# source_eagle.net
KiCad netlist of a schematic drawn in EAGLE
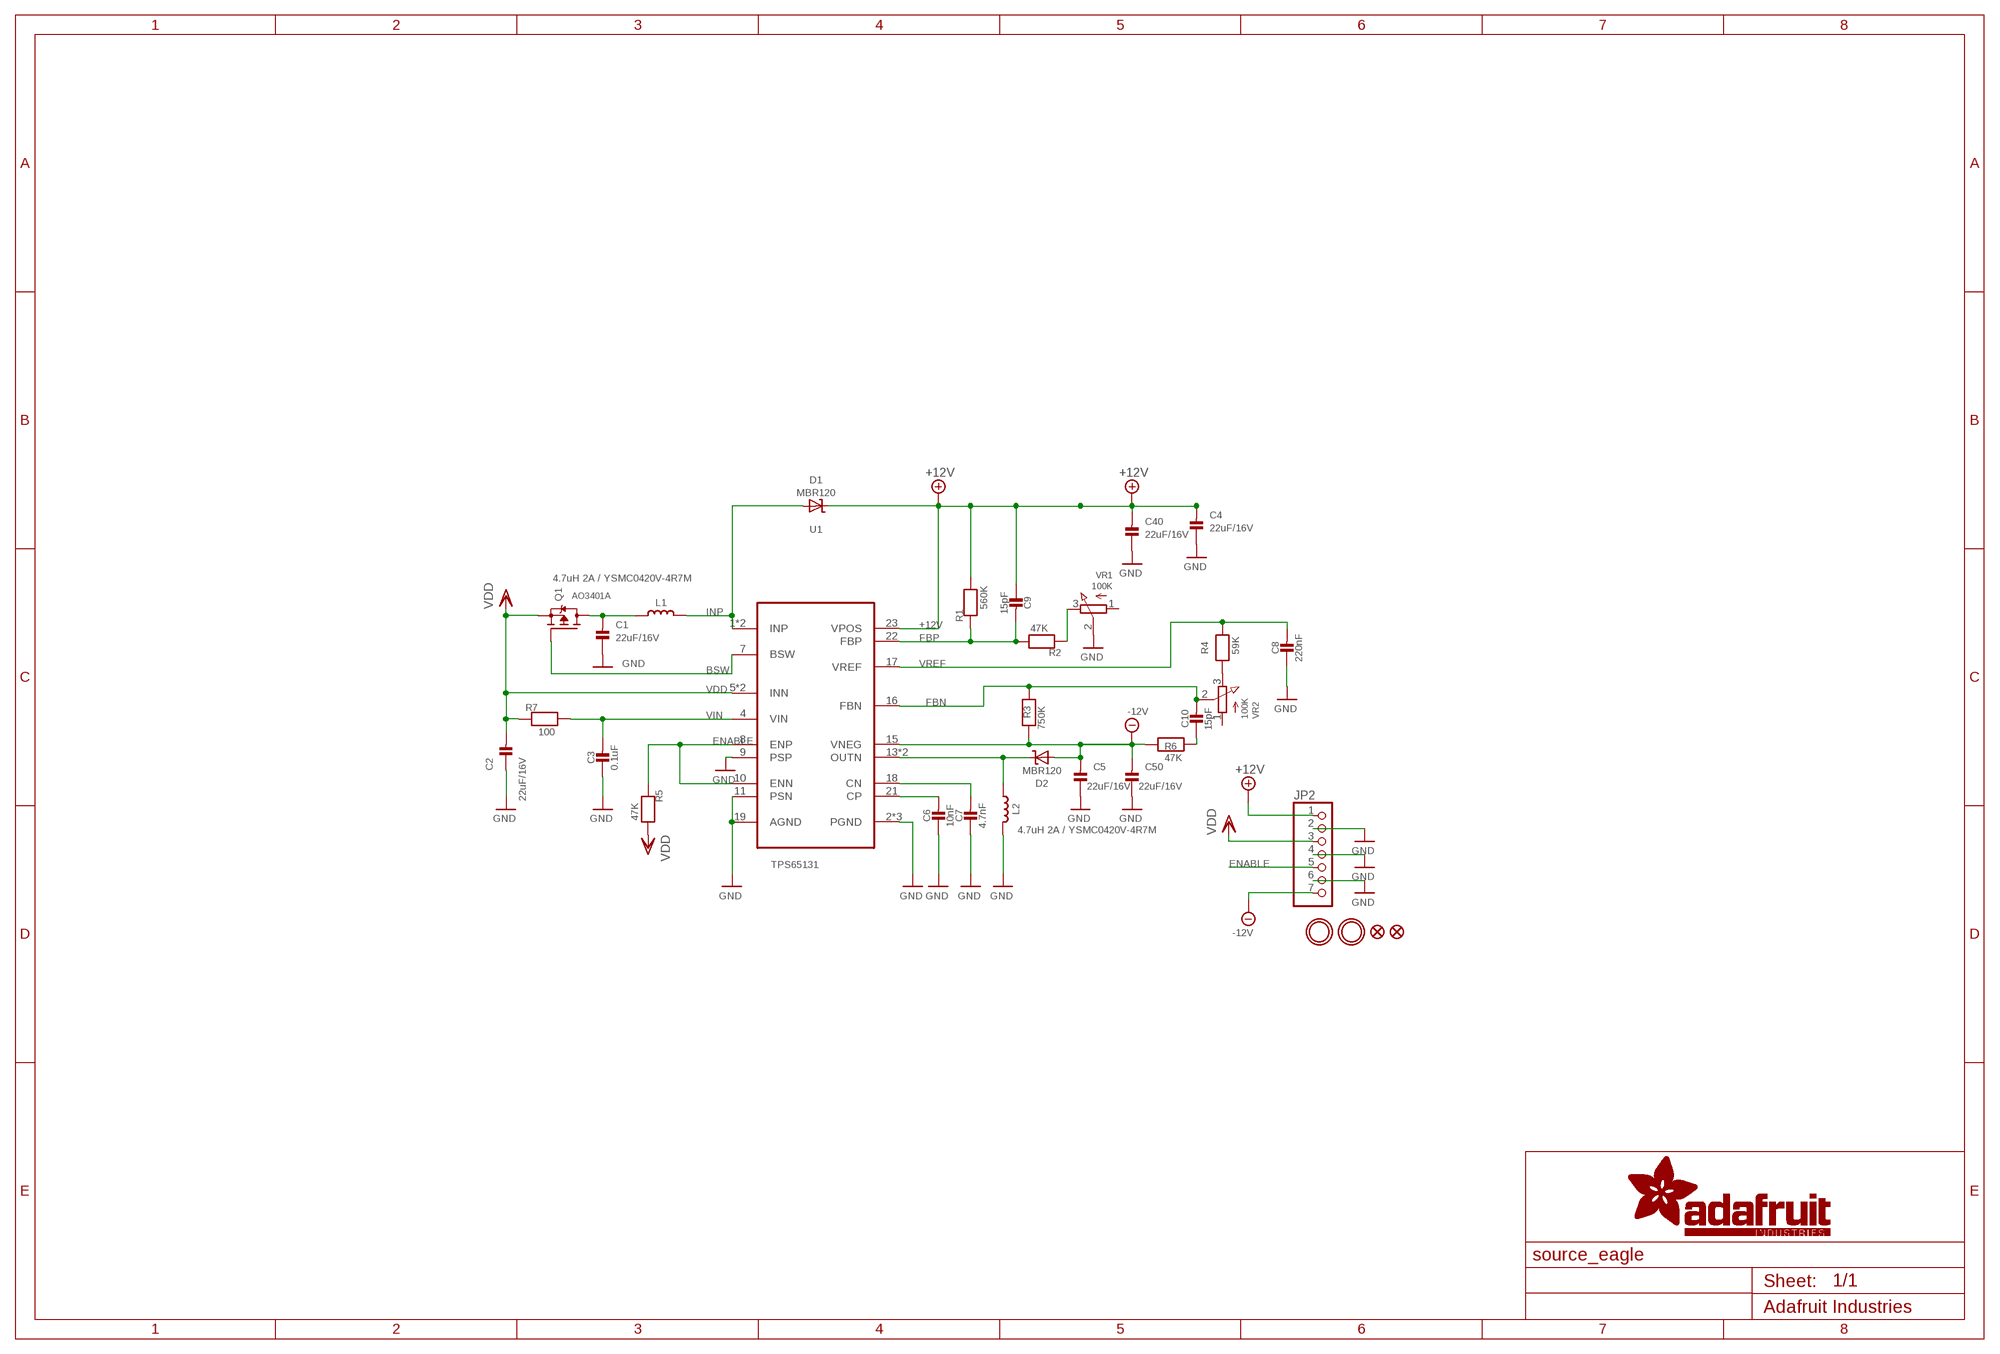
[diagram p0: schematic, sheet 1]

(export (version "E")
  (design (tool "Eeschema 10.0.6"))
  (components
    (comp (ref "C1")
      (value "22uF/16V")
      (footprint "eagle-import:0805-NO")
      (libsource (lib "eagle-import") (part "CAP_CERAMIC0805-NOOUTLINE"))
    )
    (comp (ref "C2")
      (value "22uF/16V")
      (footprint "eagle-import:0805-NO")
      (libsource (lib "eagle-import") (part "CAP_CERAMIC0805-NOOUTLINE"))
    )
    (comp (ref "C3")
      (value "0.1uF")
      (footprint "eagle-import:0603-NO")
      (libsource (lib "eagle-import") (part "CAP_CERAMIC0603_NO"))
    )
    (comp (ref "C4")
      (value "22uF/16V")
      (footprint "eagle-import:0805-NO")
      (libsource (lib "eagle-import") (part "CAP_CERAMIC0805-NOOUTLINE"))
    )
    (comp (ref "C5")
      (value "22uF/16V")
      (footprint "eagle-import:0805-NO")
      (libsource (lib "eagle-import") (part "CAP_CERAMIC0805-NOOUTLINE"))
    )
    (comp (ref "C6")
      (value "10nF")
      (footprint "eagle-import:0603-NO")
      (libsource (lib "eagle-import") (part "CAP_CERAMIC0603_NO"))
    )
    (comp (ref "C7")
      (value "4.7nF")
      (footprint "eagle-import:0603-NO")
      (libsource (lib "eagle-import") (part "CAP_CERAMIC0603_NO"))
    )
    (comp (ref "C8")
      (value "220nF")
      (footprint "eagle-import:0603-NO")
      (libsource (lib "eagle-import") (part "CAP_CERAMIC0603_NO"))
    )
    (comp (ref "C9")
      (value "15pF")
      (footprint "eagle-import:0603-NO")
      (libsource (lib "eagle-import") (part "CAP_CERAMIC0603_NO"))
    )
    (comp (ref "C10")
      (value "15pF")
      (footprint "eagle-import:0603-NO")
      (libsource (lib "eagle-import") (part "CAP_CERAMIC0603_NO"))
    )
    (comp (ref "C40")
      (value "22uF/16V")
      (footprint "eagle-import:0805-NO")
      (libsource (lib "eagle-import") (part "CAP_CERAMIC0805-NOOUTLINE"))
    )
    (comp (ref "C50")
      (value "22uF/16V")
      (footprint "eagle-import:0805-NO")
      (libsource (lib "eagle-import") (part "CAP_CERAMIC0805-NOOUTLINE"))
    )
    (comp (ref "D1")
      (value "MBR120")
      (footprint "eagle-import:SOD-123FL")
      (libsource (lib "eagle-import") (part "DIODE-SCHOTTKYSOD-123FL"))
    )
    (comp (ref "D2")
      (value "MBR120")
      (footprint "eagle-import:SOD-123FL")
      (libsource (lib "eagle-import") (part "DIODE-SCHOTTKYSOD-123FL"))
    )
    (comp (ref "FID1")
      (value "FIDUCIAL_0.5MM")
      (footprint "eagle-import:FIDUCIAL_0.5MM")
      (libsource (lib "eagle-import") (part "FIDUCIAL_0.5MM"))
    )
    (comp (ref "FID2")
      (value "FIDUCIAL_0.5MM")
      (footprint "eagle-import:FIDUCIAL_0.5MM")
      (libsource (lib "eagle-import") (part "FIDUCIAL_0.5MM"))
    )
    (comp (ref "JP2")
      (value "HEADER-1X7THICKER")
      (footprint "eagle-import:1X07_ROUND_76")
      (libsource (lib "eagle-import") (part "HEADER-1X7THICKER"))
    )
    (comp (ref "L1")
      (value "4.7uH 2A / YSMC0420V-4R7M")
      (footprint "eagle-import:INDUCTOR_4X4MM_NR401")
      (libsource (lib "eagle-import") (part "INDUCTORNR401"))
    )
    (comp (ref "L2")
      (value "4.7uH 2A / YSMC0420V-4R7M")
      (footprint "eagle-import:INDUCTOR_4X4MM_NR401")
      (libsource (lib "eagle-import") (part "INDUCTORNR401"))
    )
    (comp (ref "Q1")
      (value "AO3401A")
      (footprint "eagle-import:SOT23-WIDE")
      (libsource (lib "eagle-import") (part "MOSFET-PWIDE"))
    )
    (comp (ref "R1")
      (value "560K")
      (footprint "eagle-import:0603-NO")
      (libsource (lib "eagle-import") (part "RESISTOR_0603_NOOUT"))
    )
    (comp (ref "R2")
      (value "47K")
      (footprint "eagle-import:0603-NO")
      (libsource (lib "eagle-import") (part "RESISTOR_0603_NOOUT"))
    )
    (comp (ref "R3")
      (value "750K")
      (footprint "eagle-import:0603-NO")
      (libsource (lib "eagle-import") (part "RESISTOR_0603_NOOUT"))
    )
    (comp (ref "R4")
      (value "59K")
      (footprint "eagle-import:0603-NO")
      (libsource (lib "eagle-import") (part "RESISTOR_0603_NOOUT"))
    )
    (comp (ref "R5")
      (value "47K")
      (footprint "eagle-import:0603-NO")
      (libsource (lib "eagle-import") (part "RESISTOR_0603_NOOUT"))
    )
    (comp (ref "R6")
      (value "47K")
      (footprint "eagle-import:0603-NO")
      (libsource (lib "eagle-import") (part "RESISTOR_0603_NOOUT"))
    )
    (comp (ref "R7")
      (value "100")
      (footprint "eagle-import:0603-NO")
      (libsource (lib "eagle-import") (part "RESISTOR_0603_NOOUT"))
    )
    (comp (ref "U$1")
      (value "MOUNTINGHOLE2.5")
      (footprint "eagle-import:MOUNTINGHOLE_2.5_PLATED")
      (libsource (lib "eagle-import") (part "MOUNTINGHOLE2.5"))
    )
    (comp (ref "U$2")
      (value "MOUNTINGHOLE2.5")
      (footprint "eagle-import:MOUNTINGHOLE_2.5_PLATED")
      (libsource (lib "eagle-import") (part "MOUNTINGHOLE2.5"))
    )
    (comp (ref "U1")
      (value "TPS65131")
      (footprint "eagle-import:QFN24_4MM")
      (fields (field (name "MANUFACTURER") "Texas Instruments"))
      (libsource (lib "eagle-import") (part "TPS6513X"))
    )
    (comp (ref "VR1")
      (value "100K")
      (footprint "eagle-import:TRIMPOT_BOURNS_TC33X-2")
      (fields (field (name "ROT") "0"))
      (libsource (lib "eagle-import") (part "TRIMPOTTC33X-2"))
    )
    (comp (ref "VR2")
      (value "100K")
      (footprint "eagle-import:TRIMPOT_BOURNS_TC33X-2")
      (fields (field (name "ROT") "0"))
      (libsource (lib "eagle-import") (part "TRIMPOTTC33X-2"))
    )
  )
  (nets
    (net (code "1") (name "+12V") (class "Default")
      (node (ref "C4") (pin "2") (pinfunction "2_2") (pintype "passive"))
      (node (ref "C40") (pin "2") (pinfunction "2_2") (pintype "passive"))
      (node (ref "C9") (pin "1") (pinfunction "1_1") (pintype "passive"))
      (node (ref "D1") (pin "C") (pinfunction "C_C") (pintype "passive"))
      (node (ref "JP2") (pin "1") (pinfunction "1_1") (pintype "passive"))
      (node (ref "R1") (pin "2") (pinfunction "2_2") (pintype "passive"))
      (node (ref "U1") (pin "23") (pinfunction "VPOS_23") (pintype "bidirectional"))
    )
    (net (code "2") (name "-12V") (class "Default")
      (node (ref "C5") (pin "2") (pinfunction "2_2") (pintype "passive"))
      (node (ref "C50") (pin "2") (pinfunction "2_2") (pintype "passive"))
      (node (ref "D2") (pin "A") (pinfunction "A_A") (pintype "passive"))
      (node (ref "JP2") (pin "7") (pinfunction "7_7") (pintype "passive"))
      (node (ref "R3") (pin "1") (pinfunction "1_1") (pintype "passive"))
      (node (ref "R6") (pin "1") (pinfunction "1_1") (pintype "passive"))
      (node (ref "U1") (pin "15") (pinfunction "VNEG_15") (pintype "bidirectional"))
    )
    (net (code "3") (name "/BSW") (class "Default")
      (node (ref "Q1") (pin "1") (pinfunction "G_1") (pintype "passive"))
      (node (ref "U1") (pin "7") (pinfunction "BSW_7") (pintype "bidirectional"))
    )
    (net (code "4") (name "/ENABLE") (class "Default")
      (node (ref "JP2") (pin "5") (pinfunction "5_5") (pintype "passive"))
      (node (ref "R5") (pin "1") (pinfunction "1_1") (pintype "passive"))
      (node (ref "U1") (pin "10") (pinfunction "ENN_10") (pintype "bidirectional"))
      (node (ref "U1") (pin "8") (pinfunction "ENP_8") (pintype "bidirectional"))
    )
    (net (code "5") (name "/FBN") (class "Default")
      (node (ref "C10") (pin "2") (pinfunction "2_2") (pintype "passive"))
      (node (ref "R3") (pin "2") (pinfunction "2_2") (pintype "passive"))
      (node (ref "U1") (pin "16") (pinfunction "FBN_16") (pintype "bidirectional"))
      (node (ref "VR2") (pin "2") (pinfunction "S_2") (pintype "passive"))
    )
    (net (code "6") (name "/FBP") (class "Default")
      (node (ref "C9") (pin "2") (pinfunction "2_2") (pintype "passive"))
      (node (ref "R1") (pin "1") (pinfunction "1_1") (pintype "passive"))
      (node (ref "R2") (pin "2") (pinfunction "2_2") (pintype "passive"))
      (node (ref "U1") (pin "22") (pinfunction "FBP_22") (pintype "bidirectional"))
    )
    (net (code "7") (name "/INP") (class "Default")
      (node (ref "D1") (pin "A") (pinfunction "A_A") (pintype "passive"))
      (node (ref "L1") (pin "P$2") (pinfunction "2_P$2") (pintype "passive"))
      (node (ref "U1") (pin "1") (pinfunction "INP_1") (pintype "input"))
      (node (ref "U1") (pin "24") (pinfunction "INP_24") (pintype "input"))
    )
    (net (code "8") (name "/VIN") (class "Default")
      (node (ref "C3") (pin "2") (pinfunction "2_2") (pintype "passive"))
      (node (ref "R7") (pin "2") (pinfunction "2_2") (pintype "passive"))
      (node (ref "U1") (pin "4") (pinfunction "VIN_4") (pintype "input"))
    )
    (net (code "9") (name "/VREF") (class "Default")
      (node (ref "C8") (pin "2") (pinfunction "2_2") (pintype "passive"))
      (node (ref "R4") (pin "2") (pinfunction "2_2") (pintype "passive"))
      (node (ref "U1") (pin "17") (pinfunction "VREF_17") (pintype "input"))
    )
    (net (code "10") (name "GND") (class "Default")
      (node (ref "C1") (pin "1") (pinfunction "1_1") (pintype "passive"))
      (node (ref "C2") (pin "1") (pinfunction "1_1") (pintype "passive"))
      (node (ref "C3") (pin "1") (pinfunction "1_1") (pintype "passive"))
      (node (ref "C4") (pin "1") (pinfunction "1_1") (pintype "passive"))
      (node (ref "C40") (pin "1") (pinfunction "1_1") (pintype "passive"))
      (node (ref "C5") (pin "1") (pinfunction "1_1") (pintype "passive"))
      (node (ref "C50") (pin "1") (pinfunction "1_1") (pintype "passive"))
      (node (ref "C6") (pin "1") (pinfunction "1_1") (pintype "passive"))
      (node (ref "C7") (pin "1") (pinfunction "1_1") (pintype "passive"))
      (node (ref "C8") (pin "1") (pinfunction "1_1") (pintype "passive"))
      (node (ref "JP2") (pin "2") (pinfunction "2_2") (pintype "passive"))
      (node (ref "JP2") (pin "4") (pinfunction "4_4") (pintype "passive"))
      (node (ref "JP2") (pin "6") (pinfunction "6_6") (pintype "passive"))
      (node (ref "L2") (pin "P$2") (pinfunction "2_P$2") (pintype "passive"))
      (node (ref "U1") (pin "11") (pinfunction "PSN_11") (pintype "bidirectional"))
      (node (ref "U1") (pin "19") (pinfunction "AGND_19") (pintype "power_in"))
      (node (ref "U1") (pin "2") (pinfunction "PGND_2") (pintype "power_in"))
      (node (ref "U1") (pin "25") (pinfunction "PGND_25") (pintype "power_in"))
      (node (ref "U1") (pin "3") (pinfunction "PGND_3") (pintype "power_in"))
      (node (ref "U1") (pin "9") (pinfunction "PSP_9") (pintype "bidirectional"))
      (node (ref "VR1") (pin "2") (pinfunction "S_2") (pintype "passive"))
    )
    (net (code "11") (name "Net-(C10-Pad1)") (class "Default")
      (node (ref "C10") (pin "1") (pinfunction "1_1") (pintype "passive"))
      (node (ref "R6") (pin "2") (pinfunction "2_2") (pintype "passive"))
    )
    (net (code "12") (name "Net-(L1-1)") (class "Default")
      (node (ref "C1") (pin "2") (pinfunction "2_2") (pintype "passive"))
      (node (ref "L1") (pin "P$1") (pinfunction "1_P$1") (pintype "passive"))
      (node (ref "Q1") (pin "3") (pinfunction "D_3") (pintype "passive"))
    )
    (net (code "13") (name "Net-(L2-1)") (class "Default")
      (node (ref "D2") (pin "C") (pinfunction "C_C") (pintype "passive"))
      (node (ref "L2") (pin "P$1") (pinfunction "1_P$1") (pintype "passive"))
      (node (ref "U1") (pin "13") (pinfunction "OUTN_13") (pintype "output"))
      (node (ref "U1") (pin "14") (pinfunction "OUTN_14") (pintype "output"))
    )
    (net (code "14") (name "Net-(U1-CN)") (class "Default")
      (node (ref "C7") (pin "2") (pinfunction "2_2") (pintype "passive"))
      (node (ref "U1") (pin "18") (pinfunction "CN_18") (pintype "bidirectional"))
    )
    (net (code "15") (name "Net-(U1-CP)") (class "Default")
      (node (ref "C6") (pin "2") (pinfunction "2_2") (pintype "passive"))
      (node (ref "U1") (pin "21") (pinfunction "CP_21") (pintype "bidirectional"))
    )
    (net (code "16") (name "Net-(VR1-E)") (class "Default")
      (node (ref "R2") (pin "1") (pinfunction "1_1") (pintype "passive"))
      (node (ref "VR1") (pin "3") (pinfunction "E_3") (pintype "passive"))
    )
    (net (code "17") (name "Net-(VR2-E)") (class "Default")
      (node (ref "R4") (pin "1") (pinfunction "1_1") (pintype "passive"))
      (node (ref "VR2") (pin "3") (pinfunction "E_3") (pintype "passive"))
    )
    (net (code "18") (name "VDD") (class "Default")
      (node (ref "C2") (pin "2") (pinfunction "2_2") (pintype "passive"))
      (node (ref "JP2") (pin "3") (pinfunction "3_3") (pintype "passive"))
      (node (ref "Q1") (pin "2") (pinfunction "S_2") (pintype "passive"))
      (node (ref "R5") (pin "2") (pinfunction "2_2") (pintype "passive"))
      (node (ref "R7") (pin "1") (pinfunction "1_1") (pintype "passive"))
      (node (ref "U1") (pin "5") (pinfunction "INN_5") (pintype "input"))
      (node (ref "U1") (pin "6") (pinfunction "INN_6") (pintype "input"))
    )
    (net (code "19") (name "unconnected-(VR1-A-Pad1)") (class "Default")
      (node (ref "VR1") (pin "1") (pinfunction "A_1") (pintype "passive"))
    )
    (net (code "20") (name "unconnected-(VR2-A-Pad1)") (class "Default")
      (node (ref "VR2") (pin "1") (pinfunction "A_1") (pintype "passive"))
    )
  )
)
